# 03_Power.net
KiCad netlist of a schematic drawn in Altium Designer
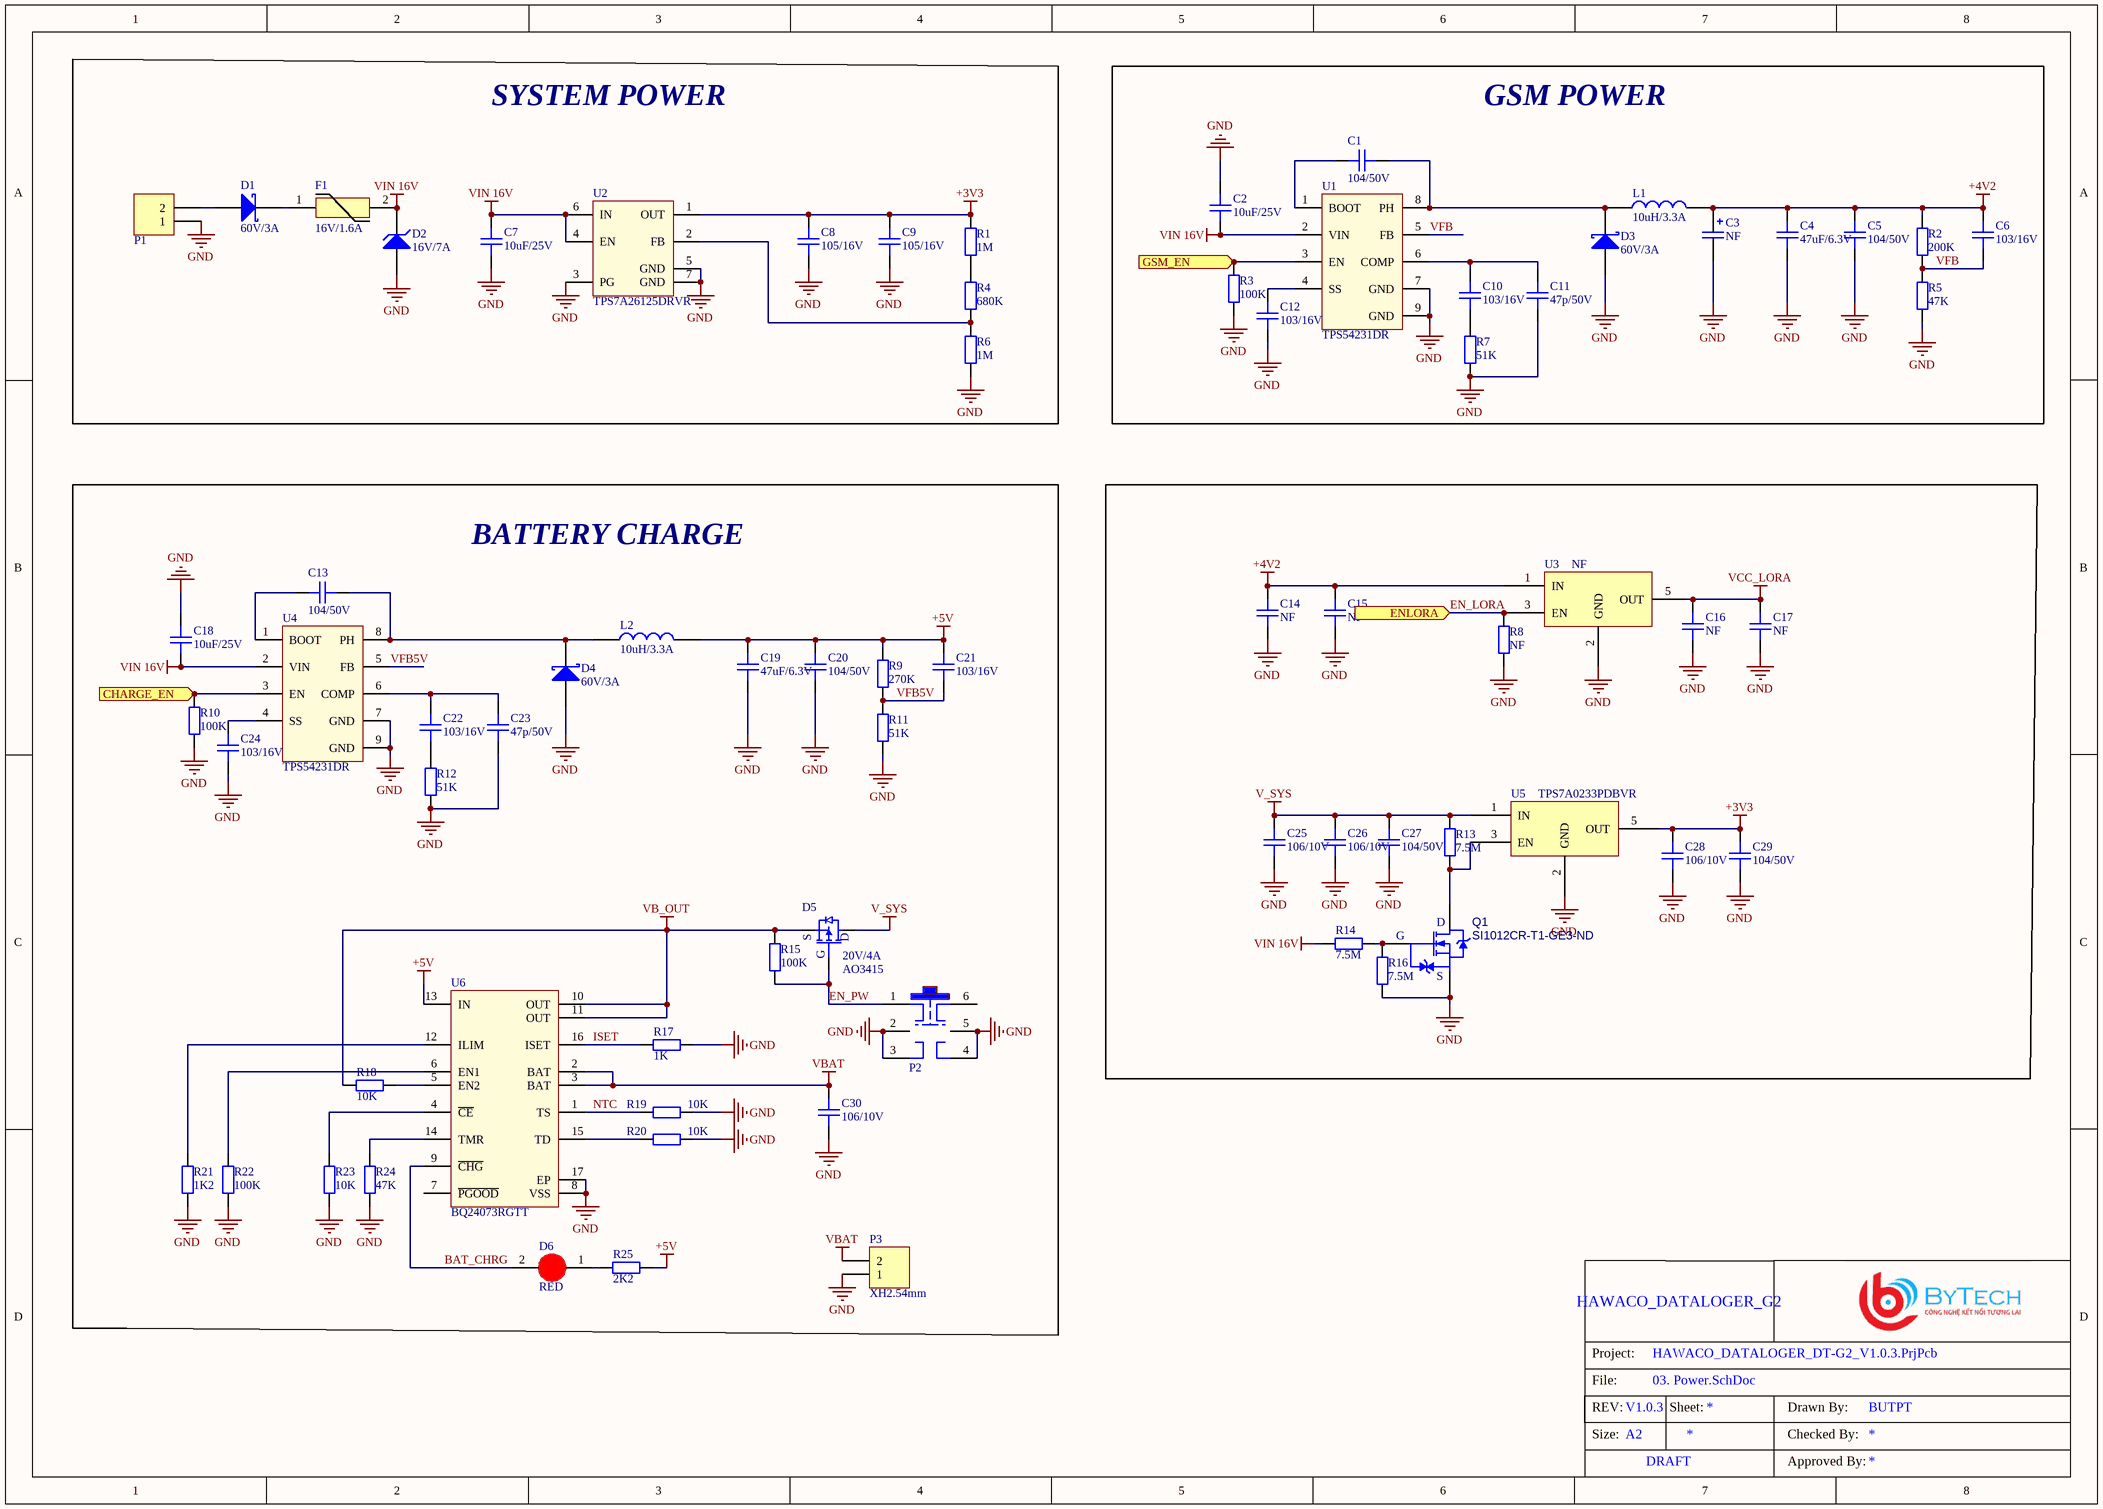
[diagram p0: 03. Power.SchDoc]

(export (version "E")
  (design (tool "Eeschema 10.0.6"))
  (components
    (comp (ref "C1")
      (value "104/50V")
      (footprint "CAPC-0603 (1608)")
      (description "CAP CER 0.1uF 50V 10% X7R 0603")
      (fields (field (name "MPN") "C0603C104K5RACTU"))
      (libsource (lib "01.Passives") (part "C0603C104K5RACTU"))
    )
    (comp (ref "C2")
      (value "10uF/25V")
      (footprint "CAPC-0805 (2012)")
      (description "CAP0805 X5R 10UF 10% 25V")
      (fields (field (name "MPN") "GMC21X5R106K25NT") (field (name "MFR") "CAL-CHIP ELECTRONICS, INC."))
      (libsource (lib "01.Passives") (part "GMC21X5R106K25NT"))
    )
    (comp (ref "C3")
      (value "NF")
      (footprint "CAP_TANTAL_1210(3528)")
      (description "CAP TANT POLY 220uF 20% 6.3V 3528 35mOhm ESR")
      (fields (field (name "MPN") "T520B227M006ATE035"))
      (libsource (lib "01.Passives") (part "T520B227M006ATE035"))
    )
    (comp (ref "C4")
      (value "47uF/6.3V")
      (footprint "CAPC-0603 (1608)")
      (description "CAP CER 47UF 6.3V X5R 0603")
      (fields (field (name "MPN") "GRM188R60J476ME15D") (field (name "MFR") "Murata Electronics"))
      (libsource (lib "01.Passives") (part "GRM188R60J476ME15D"))
    )
    (comp (ref "C5")
      (value "104/50V")
      (footprint "CAPC-0603 (1608)")
      (description "CAP CER 0.1uF 50V 10% X7R 0603")
      (fields (field (name "MPN") "C0603C104K5RACTU"))
      (libsource (lib "01.Passives") (part "C0603C104K5RACTU"))
    )
    (comp (ref "C6")
      (value "103/16V")
      (footprint "CAPC-0603 (1608)")
      (description "CAP CER 10nF 16V 10% X7R 0603")
      (fields (field (name "MPN") "CC0603KRX7R7BB103"))
      (libsource (lib "01.Passives") (part "CC0603KRX7R7BB103"))
    )
    (comp (ref "C7")
      (value "10uF/25V")
      (footprint "CAPC-0805 (2012)")
      (description "CAP0805 X5R 10UF 10% 25V")
      (fields (field (name "MPN") "GMC21X5R106K25NT") (field (name "MFR") "CAL-CHIP ELECTRONICS, INC."))
      (libsource (lib "01.Passives") (part "GMC21X5R106K25NT"))
    )
    (comp (ref "C8")
      (value "105/16V")
      (footprint "CAPC-0603 (1608)")
      (description "CAP CER 1uF 10% 16V X7R 0603")
      (fields (field (name "MPN") "CC0603KRX7R7BB105"))
      (libsource (lib "01.Passives") (part "CC0603KRX7R7BB105"))
    )
    (comp (ref "C9")
      (value "105/16V")
      (footprint "CAPC-0603 (1608)")
      (description "CAP CER 1uF 10% 16V X7R 0603")
      (fields (field (name "MPN") "CC0603KRX7R7BB105"))
      (libsource (lib "01.Passives") (part "CC0603KRX7R7BB105"))
    )
    (comp (ref "C10")
      (value "103/16V")
      (footprint "CAPC-0603 (1608)")
      (description "CAP CER 10nF 16V 10% X7R 0603")
      (fields (field (name "MPN") "CC0603KRX7R7BB103"))
      (libsource (lib "01.Passives") (part "CC0603KRX7R7BB103"))
    )
    (comp (ref "C11")
      (value "47p/50V")
      (footprint "CAPC-0603 (1608)")
      (description "CAP CER 47pF 5% 50V C0G/NP0 0603")
      (fields (field (name "MPN") "CL10C470JB8NNNC"))
      (libsource (lib "01.Passives") (part "CL10C470JB8NNNC"))
    )
    (comp (ref "C12")
      (value "103/16V")
      (footprint "CAPC-0603 (1608)")
      (description "CAP CER 10nF 16V 10% X7R 0603")
      (fields (field (name "MPN") "CC0603KRX7R7BB103"))
      (libsource (lib "01.Passives") (part "CC0603KRX7R7BB103"))
    )
    (comp (ref "C13")
      (value "104/50V")
      (footprint "CAPC-0603 (1608)")
      (description "CAP CER 0.1uF 50V 10% X7R 0603")
      (fields (field (name "MPN") "C0603C104K5RACTU"))
      (libsource (lib "01.Passives") (part "C0603C104K5RACTU"))
    )
    (comp (ref "C14")
      (value "NF")
      (footprint "CAPC-0603 (1608)")
      (description "CAP CER 10uF 10% 10V X5R 0603")
      (fields (field (name "MPN") "CL10A106KP8NNNC"))
      (libsource (lib "01.Passives") (part "CL10A106KP8NNNC"))
    )
    (comp (ref "C15")
      (value "NF")
      (footprint "CAPC-0603 (1608)")
      (description "CAP CER 0.1uF 50V 10% X7R 0603")
      (fields (field (name "MPN") "C0603C104K5RACTU"))
      (libsource (lib "01.Passives") (part "C0603C104K5RACTU"))
    )
    (comp (ref "C16")
      (value "NF")
      (footprint "CAPC-0603 (1608)")
      (description "CAP CER 10uF 10% 10V X5R 0603")
      (fields (field (name "MPN") "CL10A106KP8NNNC"))
      (libsource (lib "01.Passives") (part "CL10A106KP8NNNC"))
    )
    (comp (ref "C17")
      (value "NF")
      (footprint "CAPC-0603 (1608)")
      (description "CAP CER 0.1uF 50V 10% X7R 0603")
      (fields (field (name "MPN") "C0603C104K5RACTU"))
      (libsource (lib "01.Passives") (part "C0603C104K5RACTU"))
    )
    (comp (ref "C18")
      (value "10uF/25V")
      (footprint "CAPC-0805 (2012)")
      (description "CAP0805 X5R 10UF 10% 25V")
      (fields (field (name "MPN") "GMC21X5R106K25NT") (field (name "MFR") "CAL-CHIP ELECTRONICS, INC."))
      (libsource (lib "01.Passives") (part "GMC21X5R106K25NT"))
    )
    (comp (ref "C19")
      (value "47uF/6.3V")
      (footprint "CAPC-0603 (1608)")
      (description "CAP CER 47UF 6.3V X5R 0603")
      (fields (field (name "MPN") "GRM188R60J476ME15D") (field (name "MFR") "Murata Electronics"))
      (libsource (lib "01.Passives") (part "GRM188R60J476ME15D"))
    )
    (comp (ref "C20")
      (value "104/50V")
      (footprint "CAPC-0603 (1608)")
      (description "CAP CER 0.1uF 50V 10% X7R 0603")
      (fields (field (name "MPN") "C0603C104K5RACTU"))
      (libsource (lib "01.Passives") (part "C0603C104K5RACTU"))
    )
    (comp (ref "C21")
      (value "103/16V")
      (footprint "CAPC-0603 (1608)")
      (description "CAP CER 10nF 16V 10% X7R 0603")
      (fields (field (name "MPN") "CC0603KRX7R7BB103"))
      (libsource (lib "01.Passives") (part "CC0603KRX7R7BB103"))
    )
    (comp (ref "C22")
      (value "103/16V")
      (footprint "CAPC-0603 (1608)")
      (description "CAP CER 10nF 16V 10% X7R 0603")
      (fields (field (name "MPN") "CC0603KRX7R7BB103"))
      (libsource (lib "01.Passives") (part "CC0603KRX7R7BB103"))
    )
    (comp (ref "C23")
      (value "47p/50V")
      (footprint "CAPC-0603 (1608)")
      (description "CAP CER 47pF 5% 50V C0G/NP0 0603")
      (fields (field (name "MPN") "CL10C470JB8NNNC"))
      (libsource (lib "01.Passives") (part "CL10C470JB8NNNC"))
    )
    (comp (ref "C24")
      (value "103/16V")
      (footprint "CAPC-0603 (1608)")
      (description "CAP CER 10nF 16V 10% X7R 0603")
      (fields (field (name "MPN") "CC0603KRX7R7BB103"))
      (libsource (lib "01.Passives") (part "CC0603KRX7R7BB103"))
    )
    (comp (ref "C25")
      (value "106/10V")
      (footprint "CAPC-0603 (1608)")
      (description "CAP CER 10uF 10% 10V X5R 0603")
      (fields (field (name "MPN") "CL10A106KP8NNNC"))
      (libsource (lib "01.Passives") (part "CL10A106KP8NNNC"))
    )
    (comp (ref "C26")
      (value "106/10V")
      (footprint "CAPC-0603 (1608)")
      (description "CAP CER 10uF 10% 10V X5R 0603")
      (fields (field (name "MPN") "CL10A106KP8NNNC"))
      (libsource (lib "01.Passives") (part "CL10A106KP8NNNC"))
    )
    (comp (ref "C27")
      (value "104/50V")
      (footprint "CAPC-0603 (1608)")
      (description "CAP CER 0.1uF 50V 10% X7R 0603")
      (fields (field (name "MPN") "C0603C104K5RACTU"))
      (libsource (lib "01.Passives") (part "C0603C104K5RACTU"))
    )
    (comp (ref "C28")
      (value "106/10V")
      (footprint "CAPC-0603 (1608)")
      (description "CAP CER 10uF 10% 10V X5R 0603")
      (fields (field (name "MPN") "CL10A106KP8NNNC"))
      (libsource (lib "01.Passives") (part "CL10A106KP8NNNC"))
    )
    (comp (ref "C29")
      (value "104/50V")
      (footprint "CAPC-0603 (1608)")
      (description "CAP CER 0.1uF 50V 10% X7R 0603")
      (fields (field (name "MPN") "C0603C104K5RACTU"))
      (libsource (lib "01.Passives") (part "C0603C104K5RACTU"))
    )
    (comp (ref "C30")
      (value "106/10V")
      (footprint "CAPC-0603 (1608)")
      (description "CAP CER 10uF 10% 10V X5R 0603")
      (fields (field (name "MPN") "CL10A106KP8NNNC"))
      (libsource (lib "01.Passives") (part "CL10A106KP8NNNC"))
    )
    (comp (ref "D1")
      (value "60V/3A")
      (footprint "DIODE_DO214AC_SMA")
      (description "DIODE SCHOTTKY 60V 3A DO214AC")
      (fields (field (name "MPN") "SK36A-LTP"))
      (libsource (lib "03.Semiconductor") (part "SK36A-LTP"))
    )
    (comp (ref "D2")
      (value "16V/7A")
      (footprint "SOD123")
      (description "TVS DIODE 16VWM 26VC SOD123FL")
      (fields (field (name "MPN") "1SMF16BT3") (field (name "MFR") "ON Semiconductor"))
      (libsource (lib "03.Semiconductor") (part "1SMF16BT3"))
    )
    (comp (ref "D3")
      (value "60V/3A")
      (footprint "DIODE_DO214AC_SMA")
      (description "DIODE SCHOTTKY 60V 3A DO214AC")
      (fields (field (name "MPN") "SK36A-LTP") (field (name "MANUFACTURER") "Micro Commercial Co"))
      (libsource (lib "03.Semiconductor") (part "SK36A-LTP"))
    )
    (comp (ref "D4")
      (value "60V/3A")
      (footprint "DIODE_DO214AC_SMA")
      (description "DIODE SCHOTTKY 60V 3A DO214AC")
      (fields (field (name "MPN") "SK36A-LTP") (field (name "MANUFACTURER") "Micro Commercial Co"))
      (libsource (lib "03.Semiconductor") (part "SK36A-LTP"))
    )
    (comp (ref "D5")
      (value "20V/4A")
      (footprint "SOT23_3")
      (description "MOSFET P-CH 20V 4A SOT23")
      (fields (field (name "MFR") "Alpha & Omega Semiconductor Inc.") (field (name "MPN") "AO3415"))
      (libsource (lib "03.Semiconductor") (part "AO3415"))
    )
    (comp (ref "D6")
      (value "RED")
      (footprint "LED 0603")
      (description "LED 0603 RED")
      (libsource (lib "03.Semiconductor") (part "LED 0603 RED"))
    )
    (comp (ref "F1")
      (value "16V/1.6A")
      (footprint "FUSE_1812(4532)")
      (description "PTC RESET FUSE 16V 1.6A 1812")
      (fields (field (name "MPN") "MPTS1812L16016R") (field (name "MFR") "Meritek"))
      (libsource (lib "02.Power,Protection") (part "MPTS1812L16016R"))
    )
    (comp (ref "L1")
      (value "10uH/3.3A")
      (footprint "IND-74404084150")
      (description "FIXED IND 10UH 3.3A 38 MOHM SMD")
      (fields
        (field (name "MPN") "SWPA8040S100MT")
        (field (name "MFR") "Shenzhen Sunlord Electronics Co., Ltd.")
      )
      (libsource (lib "01.Passives") (part "SWPA8040S100MT"))
    )
    (comp (ref "L2")
      (value "10uH/3.3A")
      (footprint "IND-74404084150")
      (description "FIXED IND 10UH 3.3A 38 MOHM SMD")
      (fields
        (field (name "MPN") "SWPA8040S100MT")
        (field (name "MFR") "Shenzhen Sunlord Electronics Co., Ltd.")
      )
      (libsource (lib "01.Passives") (part "SWPA8040S100MT"))
    )
    (comp (ref "P1")
      (value "15EDG3.81-2P")
      (footprint "HDR_3.81MM_RA_2x1")
      (description "Pluggable terminal 15EDG- 2P 3.81MM")
      (fields (field (name "MFR") "China"))
      (libsource (lib "04.Header-Connecter") (part "15EDG3.81-2P"))
    )
    (comp (ref "P2")
      (value "~")
      (footprint "KFC8x8")
      (description "Self-locking button 6p 8x8mm")
      (fields (field (name "MPN") "KFC8X8") (field (name "MFR") "China"))
      (libsource (lib "08.Miscellaneous") (part "KFC8X8"))
    )
    (comp (ref "P3")
      (value "XH2.54mm")
      (footprint "XH2.54-2P")
      (description "XH2.54mmm - 2P 180 degree")
      (fields (field (name "MPN") "XH-2A"))
      (libsource (lib "04.Header-Connecter") (part "XH-2A"))
    )
    (comp (ref "Q1")
      (value "SI1012CR-T1-GE3-ND")
      (footprint "SOT-416")
      (description "MOSFET N-CH 20V 0.63A SC-75A")
      (libsource (lib "03.Semiconductor") (part "SI1012CR-T1-GE3-ND"))
    )
    (comp (ref "R1")
      (value "1M")
      (footprint "RESC-0603 (1608)")
      (description "RES SMD 1M OHM 1% 1/10W 0603")
      (fields (field (name "MPN") "CRCW06031M00FKEA"))
      (libsource (lib "01.Passives") (part "CRCW06031M00FKEA"))
    )
    (comp (ref "R2")
      (value "200K")
      (footprint "RESC-0603 (1608)")
      (description "RES SMD 200K OHM 1% 1/10W 0603")
      (fields (field (name "MPN") "CR0603-FX-2003ELF"))
      (libsource (lib "01.Passives") (part "CR0603-FX-2003ELF"))
    )
    (comp (ref "R3")
      (value "100K")
      (footprint "RESC-0603 (1608)")
      (description "RES SMD 100K OHM 1% 1/10W 0603")
      (fields (field (name "MPN") "RC0603FR-07100KL"))
      (libsource (lib "01.Passives") (part "RC0603FR-07100KL"))
    )
    (comp (ref "R4")
      (value "680K")
      (footprint "RESC-0603 (1608)")
      (description "RES SMD 680K OHM 1% 1/10W 0603")
      (fields (field (name "MPN") "RT0603FRE07680KL") (field (name "MFR") "YAGEO"))
      (libsource (lib "01.Passives") (part "RT0603FRE07680KL"))
    )
    (comp (ref "R5")
      (value "47K")
      (footprint "RESC-0603 (1608)")
      (description "RES SMD 47K OHM 1% 1/10W 0603")
      (fields (field (name "MPN") "RC0603FR0747KL"))
      (libsource (lib "01.Passives") (part "RC0603FR0747KL"))
    )
    (comp (ref "R6")
      (value "1M")
      (footprint "RESC-0603 (1608)")
      (description "RES SMD 1M OHM 1% 1/10W 0603")
      (fields (field (name "MPN") "CRCW06031M00FKEA"))
      (libsource (lib "01.Passives") (part "CRCW06031M00FKEA"))
    )
    (comp (ref "R7")
      (value "51K")
      (footprint "RESC-0603 (1608)")
      (description "RES SMD 51K OHM 1% 1/10W 0603")
      (fields (field (name "MPN") "RC0603FR-0751KL") (field (name "MFR") "Yageo"))
      (libsource (lib "01.Passives") (part "RC0603FR-0751KL"))
    )
    (comp (ref "R8")
      (value "NF")
      (footprint "RESC-0603 (1608)")
      (description "RES SMD 100K OHM 1% 1/10W 0603")
      (fields (field (name "MPN") "RC0603FR-07100KL"))
      (libsource (lib "01.Passives") (part "RC0603FR-07100KL"))
    )
    (comp (ref "R9")
      (value "270K")
      (footprint "RESC-0603 (1608)")
      (description "RES SMD 270K OHM 0.1% 1/10W 0603")
      (fields (field (name "MPN") "RT0603BRD07270KL"))
      (libsource (lib "01.Passives") (part "RT0603BRD07270KL"))
    )
    (comp (ref "R10")
      (value "100K")
      (footprint "RESC-0603 (1608)")
      (description "RES SMD 100K OHM 1% 1/10W 0603")
      (fields (field (name "MPN") "RC0603FR-07100KL"))
      (libsource (lib "01.Passives") (part "RC0603FR-07100KL"))
    )
    (comp (ref "R11")
      (value "51K")
      (footprint "RESC-0603 (1608)")
      (description "RES SMD 51K OHM 1% 1/10W 0603")
      (fields (field (name "MPN") "RC0603FR-0751KL") (field (name "MFR") "Yageo"))
      (libsource (lib "01.Passives") (part "RC0603FR-0751KL"))
    )
    (comp (ref "R12")
      (value "51K")
      (footprint "RESC-0603 (1608)")
      (description "RES SMD 51K OHM 1% 1/10W 0603")
      (fields (field (name "MPN") "RC0603FR-0751KL") (field (name "MFR") "Yageo"))
      (libsource (lib "01.Passives") (part "RC0603FR-0751KL"))
    )
    (comp (ref "R13")
      (value "7.5M")
      (footprint "RESC-0603 (1608)")
      (description "RES SMD 7.5M OHM 1% 1/10W 0603")
      (fields (field (name "MPN") "RC0603FR-077M5L"))
      (libsource (lib "01.Passives") (part "RC0603FR-077M5L"))
    )
    (comp (ref "R14")
      (value "7.5M")
      (footprint "RESC-0603 (1608)")
      (description "RES SMD 7.5M OHM 1% 1/10W 0603")
      (fields (field (name "MPN") "RC0603FR-077M5L"))
      (libsource (lib "") (part "RC0603FR-077M5L_1"))
    )
    (comp (ref "R15")
      (value "100K")
      (footprint "RESC-0603 (1608)")
      (description "RES SMD 100K OHM 1% 1/10W 0603")
      (fields (field (name "MPN") "RC0603FR-07100KL"))
      (libsource (lib "01.Passives") (part "RC0603FR-07100KL"))
    )
    (comp (ref "R16")
      (value "7.5M")
      (footprint "RESC-0603 (1608)")
      (description "RES SMD 7.5M OHM 1% 1/10W 0603")
      (fields (field (name "MPN") "RC0603FR-077M5L"))
      (libsource (lib "01.Passives") (part "RC0603FR-077M5L"))
    )
    (comp (ref "R17")
      (value "1K")
      (footprint "RESC-0603 (1608)")
      (description "RES SMD 1 KOHM 1% 1/10W 0603")
      (fields (field (name "MPN") "RC0603FR-071KL"))
      (libsource (lib "01.Passives") (part "RC0603FR-071KL"))
    )
    (comp (ref "R18")
      (value "10K")
      (footprint "RESC-0603 (1608)")
      (description "RES SMD 10K OHM 1% 1/10W 0603")
      (fields (field (name "MPN") "RC0603FR-0710KL"))
      (libsource (lib "") (part "RC0603FR-0710KL_1"))
    )
    (comp (ref "R19")
      (value "10K")
      (footprint "RESC-0603 (1608)")
      (description "RES SMD 10K OHM 1% 1/10W 0603")
      (fields (field (name "MPN") "RC0603FR-0710KL"))
      (libsource (lib "") (part "RC0603FR-0710KL_1"))
    )
    (comp (ref "R20")
      (value "10K")
      (footprint "RESC-0603 (1608)")
      (description "RES SMD 10K OHM 1% 1/10W 0603")
      (fields (field (name "MPN") "RC0603FR-0710KL"))
      (libsource (lib "") (part "RC0603FR-0710KL_1"))
    )
    (comp (ref "R21")
      (value "1K2")
      (footprint "RESC-0603 (1608)")
      (description "RES SMD 1.2K OHM 1% 1/10W 0603")
      (fields (field (name "MPN") "RC0603FR-071K2L"))
      (libsource (lib "01.Passives") (part "RC0603FR-071K2L"))
    )
    (comp (ref "R22")
      (value "100K")
      (footprint "RESC-0603 (1608)")
      (description "RES SMD 100K OHM 1% 1/10W 0603")
      (fields (field (name "MPN") "RC0603FR-07100KL"))
      (libsource (lib "01.Passives") (part "RC0603FR-07100KL"))
    )
    (comp (ref "R23")
      (value "10K")
      (footprint "RESC-0603 (1608)")
      (description "RES SMD 10K OHM 1% 1/10W 0603")
      (fields (field (name "MPN") "RC0603FR-0710KL"))
      (libsource (lib "01.Passives") (part "RC0603FR-0710KL"))
    )
    (comp (ref "R24")
      (value "47K")
      (footprint "RESC-0603 (1608)")
      (description "RES SMD 47K OHM 1% 1/10W 0603")
      (fields (field (name "MPN") "RC0603FR0747KL"))
      (libsource (lib "01.Passives") (part "RC0603FR0747KL"))
    )
    (comp (ref "R25")
      (value "2K2")
      (footprint "RESC-0603 (1608)")
      (description "RES SMD 2.2K OHM 1% 1/10W 0603")
      (fields (field (name "MPN") "CRCW06032K20FKEA"))
      (libsource (lib "01.Passives") (part "CRCW06032K20FKEA"))
    )
    (comp (ref "U1")
      (value "TPS54231DR")
      (footprint "SOIC8 - TP")
      (description "IC REG BUCK ADJUSTABLE 2A 8SOIC")
      (fields (field (name "MFR") "TI"))
      (libsource (lib "05.IC") (part "TPS54231DR"))
    )
    (comp (ref "U2")
      (value "TPS7A26125DRVR")
      (footprint "WSON6")
      (description "IC REG LINEAR 1.25V 500MA 6WSON")
      (fields (field (name "MFR") "TI"))
      (libsource (lib "05.IC") (part "TPS7A26125DRVR"))
    )
    (comp (ref "U3")
      (value "NF")
      (footprint "SOT23-5")
      (description "NANOPOWER LDO")
      (fields (field (name "MPN") "TPS7A0233PDBVR"))
      (libsource (lib "05.IC") (part "TPS7A0233PDBVR"))
    )
    (comp (ref "U4")
      (value "TPS54231DR")
      (footprint "SOIC8 - TP")
      (description "IC REG BUCK ADJUSTABLE 2A 8SOIC")
      (fields (field (name "MFR") "TI"))
      (libsource (lib "05.IC") (part "TPS54231DR"))
    )
    (comp (ref "U5")
      (value "TPS7A0233PDBVR")
      (footprint "SOT23-5")
      (description "NANOPOWER LDO")
      (libsource (lib "05.IC") (part "TPS7A0233PDBVR"))
    )
    (comp (ref "U6")
      (value "BQ24073RGTT")
      (footprint "RGT16-1700X1700TP")
      (description "IC LI-ION CHARGE/PWR MGMT 16-QFN")
      (fields (field (name "MFR") "Texas Instruments"))
      (libsource (lib "05.IC") (part "BQ24073RGTT"))
    )
  )
  (nets
    (net (code "1") (name "+3V3") (class "Default")
      (node (ref "C28") (pin "2") (pinfunction "2_2") (pintype "passive"))
      (node (ref "C29") (pin "2") (pinfunction "2_2") (pintype "passive"))
      (node (ref "C8") (pin "2") (pinfunction "2_2") (pintype "passive"))
      (node (ref "C9") (pin "2") (pinfunction "2_2") (pintype "passive"))
      (node (ref "R1") (pin "2") (pinfunction "2_2") (pintype "passive"))
      (node (ref "U2") (pin "1") (pinfunction "OUT_1") (pintype "power_in"))
      (node (ref "U5") (pin "5") (pinfunction "OUT_5") (pintype "passive"))
    )
    (net (code "2") (name "+4V2") (class "Default")
      (node (ref "C14") (pin "2") (pinfunction "2_2") (pintype "passive"))
      (node (ref "C15") (pin "2") (pinfunction "2_2") (pintype "passive"))
      (node (ref "C3") (pin "1") (pinfunction "1_1") (pintype "passive"))
      (node (ref "C4") (pin "2") (pinfunction "2_2") (pintype "passive"))
      (node (ref "C5") (pin "2") (pinfunction "2_2") (pintype "passive"))
      (node (ref "C6") (pin "2") (pinfunction "2_2") (pintype "passive"))
      (node (ref "L1") (pin "2") (pinfunction "2_2") (pintype "passive"))
      (node (ref "R2") (pin "2") (pinfunction "2_2") (pintype "passive"))
      (node (ref "U3") (pin "1") (pinfunction "IN_1") (pintype "passive"))
    )
    (net (code "3") (name "+5V") (class "Default")
      (node (ref "C19") (pin "2") (pinfunction "2_2") (pintype "passive"))
      (node (ref "C20") (pin "2") (pinfunction "2_2") (pintype "passive"))
      (node (ref "C21") (pin "2") (pinfunction "2_2") (pintype "passive"))
      (node (ref "L2") (pin "2") (pinfunction "2_2") (pintype "passive"))
      (node (ref "R25") (pin "2") (pinfunction "2_2") (pintype "passive"))
      (node (ref "R9") (pin "2") (pinfunction "2_2") (pintype "passive"))
      (node (ref "U6") (pin "13") (pinfunction "IN_13") (pintype "power_in"))
    )
    (net (code "4") (name "/BAT_CHRG") (class "Default")
      (node (ref "D6") (pin "2") (pinfunction "K_2") (pintype "passive"))
      (node (ref "U6") (pin "9") (pinfunction "~{CHG}_9") (pintype "power_in"))
    )
    (net (code "5") (name "/CHARGE_EN") (class "Default")
      (node (ref "R10") (pin "2") (pinfunction "2_2") (pintype "passive"))
      (node (ref "U4") (pin "3") (pinfunction "EN_3") (pintype "passive"))
    )
    (net (code "6") (name "/EN_LORA") (class "Default")
      (node (ref "R8") (pin "2") (pinfunction "2_2") (pintype "passive"))
      (node (ref "U3") (pin "3") (pinfunction "EN_3") (pintype "passive"))
    )
    (net (code "7") (name "/EN_PW") (class "Default")
      (node (ref "D5") (pin "1") (pinfunction "G_1") (pintype "passive"))
      (node (ref "P2") (pin "1") (pinfunction "1_1") (pintype "passive"))
      (node (ref "R15") (pin "1") (pinfunction "1_1") (pintype "passive"))
    )
    (net (code "8") (name "/GSM_EN") (class "Default")
      (node (ref "R3") (pin "2") (pinfunction "2_2") (pintype "passive"))
      (node (ref "U1") (pin "3") (pinfunction "EN_3") (pintype "passive"))
    )
    (net (code "9") (name "/ISET") (class "Default")
      (node (ref "R17") (pin "1") (pinfunction "1_1") (pintype "passive"))
      (node (ref "U6") (pin "16") (pinfunction "ISET_16") (pintype "power_in"))
    )
    (net (code "10") (name "/NTC") (class "Default")
      (node (ref "R19") (pin "1") (pinfunction "1_1") (pintype "passive"))
      (node (ref "U6") (pin "1") (pinfunction "TS_1") (pintype "power_in"))
    )
    (net (code "11") (name "/VFB") (class "Default")
      (node (ref "C6") (pin "1") (pinfunction "1_1") (pintype "passive"))
      (node (ref "R2") (pin "1") (pinfunction "1_1") (pintype "passive"))
      (node (ref "R5") (pin "2") (pinfunction "2_2") (pintype "passive"))
      (node (ref "U1") (pin "5") (pinfunction "FB_5") (pintype "power_in"))
    )
    (net (code "12") (name "/VFB5V") (class "Default")
      (node (ref "C21") (pin "1") (pinfunction "1_1") (pintype "passive"))
      (node (ref "R11") (pin "2") (pinfunction "2_2") (pintype "passive"))
      (node (ref "R9") (pin "1") (pinfunction "1_1") (pintype "passive"))
      (node (ref "U4") (pin "5") (pinfunction "FB_5") (pintype "power_in"))
    )
    (net (code "13") (name "GND") (class "Default")
      (node (ref "C11") (pin "1") (pinfunction "1_1") (pintype "passive"))
      (node (ref "C12") (pin "2") (pinfunction "2_2") (pintype "passive"))
      (node (ref "C14") (pin "1") (pinfunction "1_1") (pintype "passive"))
      (node (ref "C15") (pin "1") (pinfunction "1_1") (pintype "passive"))
      (node (ref "C16") (pin "1") (pinfunction "1_1") (pintype "passive"))
      (node (ref "C17") (pin "1") (pinfunction "1_1") (pintype "passive"))
      (node (ref "C18") (pin "1") (pinfunction "1_1") (pintype "passive"))
      (node (ref "C19") (pin "1") (pinfunction "1_1") (pintype "passive"))
      (node (ref "C2") (pin "1") (pinfunction "1_1") (pintype "passive"))
      (node (ref "C20") (pin "1") (pinfunction "1_1") (pintype "passive"))
      (node (ref "C23") (pin "1") (pinfunction "1_1") (pintype "passive"))
      (node (ref "C24") (pin "2") (pinfunction "2_2") (pintype "passive"))
      (node (ref "C25") (pin "1") (pinfunction "1_1") (pintype "passive"))
      (node (ref "C26") (pin "1") (pinfunction "1_1") (pintype "passive"))
      (node (ref "C27") (pin "1") (pinfunction "1_1") (pintype "passive"))
      (node (ref "C28") (pin "1") (pinfunction "1_1") (pintype "passive"))
      (node (ref "C29") (pin "1") (pinfunction "1_1") (pintype "passive"))
      (node (ref "C3") (pin "2") (pinfunction "2_2") (pintype "passive"))
      (node (ref "C30") (pin "1") (pinfunction "1_1") (pintype "passive"))
      (node (ref "C4") (pin "1") (pinfunction "1_1") (pintype "passive"))
      (node (ref "C5") (pin "1") (pinfunction "1_1") (pintype "passive"))
      (node (ref "C7") (pin "1") (pinfunction "1_1") (pintype "passive"))
      (node (ref "C8") (pin "1") (pinfunction "1_1") (pintype "passive"))
      (node (ref "C9") (pin "1") (pinfunction "1_1") (pintype "passive"))
      (node (ref "D2") (pin "1") (pinfunction "A_1") (pintype "passive"))
      (node (ref "D3") (pin "1") (pinfunction "A_1") (pintype "passive"))
      (node (ref "D4") (pin "1") (pinfunction "A_1") (pintype "passive"))
      (node (ref "P1") (pin "1") (pinfunction "1_1") (pintype "passive"))
      (node (ref "P2") (pin "2") (pinfunction "2_2") (pintype "passive"))
      (node (ref "P2") (pin "3") (pinfunction "3_3") (pintype "passive"))
      (node (ref "P2") (pin "4") (pinfunction "4_4") (pintype "passive"))
      (node (ref "P2") (pin "5") (pinfunction "5_5") (pintype "passive"))
      (node (ref "P3") (pin "1") (pinfunction "1_1") (pintype "passive"))
      (node (ref "Q1") (pin "2") (pinfunction "S_2") (pintype "passive"))
      (node (ref "R10") (pin "1") (pinfunction "1_1") (pintype "passive"))
      (node (ref "R11") (pin "1") (pinfunction "1_1") (pintype "passive"))
      (node (ref "R12") (pin "1") (pinfunction "1_1") (pintype "passive"))
      (node (ref "R16") (pin "1") (pinfunction "1_1") (pintype "passive"))
      (node (ref "R17") (pin "2") (pinfunction "2_2") (pintype "passive"))
      (node (ref "R19") (pin "2") (pinfunction "2_2") (pintype "passive"))
      (node (ref "R20") (pin "2") (pinfunction "2_2") (pintype "passive"))
      (node (ref "R21") (pin "1") (pinfunction "1_1") (pintype "passive"))
      (node (ref "R22") (pin "1") (pinfunction "1_1") (pintype "passive"))
      (node (ref "R23") (pin "1") (pinfunction "1_1") (pintype "passive"))
      (node (ref "R24") (pin "1") (pinfunction "1_1") (pintype "passive"))
      (node (ref "R3") (pin "1") (pinfunction "1_1") (pintype "passive"))
      (node (ref "R5") (pin "1") (pinfunction "1_1") (pintype "passive"))
      (node (ref "R6") (pin "1") (pinfunction "1_1") (pintype "passive"))
      (node (ref "R7") (pin "1") (pinfunction "1_1") (pintype "passive"))
      (node (ref "R8") (pin "1") (pinfunction "1_1") (pintype "passive"))
      (node (ref "U1") (pin "7") (pinfunction "GND_7") (pintype "power_in"))
      (node (ref "U1") (pin "9") (pinfunction "GND_9") (pintype "power_in"))
      (node (ref "U2") (pin "3") (pinfunction "PG_3") (pintype "power_in"))
      (node (ref "U2") (pin "5") (pinfunction "GND_5") (pintype "power_in"))
      (node (ref "U2") (pin "7") (pinfunction "GND_7") (pintype "power_in"))
      (node (ref "U3") (pin "2") (pinfunction "GND_2") (pintype "passive"))
      (node (ref "U4") (pin "7") (pinfunction "GND_7") (pintype "power_in"))
      (node (ref "U4") (pin "9") (pinfunction "GND_9") (pintype "power_in"))
      (node (ref "U5") (pin "2") (pinfunction "GND_2") (pintype "passive"))
      (node (ref "U6") (pin "17") (pinfunction "EP_17") (pintype "power_in"))
      (node (ref "U6") (pin "8") (pinfunction "VSS_8") (pintype "power_in"))
    )
    (net (code "14") (name "Net-(C10-Pad2)") (class "Default")
      (node (ref "C10") (pin "2") (pinfunction "2_2") (pintype "passive"))
      (node (ref "R7") (pin "2") (pinfunction "2_2") (pintype "passive"))
    )
    (net (code "15") (name "Net-(C22-Pad2)") (class "Default")
      (node (ref "C22") (pin "2") (pinfunction "2_2") (pintype "passive"))
      (node (ref "R12") (pin "2") (pinfunction "2_2") (pintype "passive"))
    )
    (net (code "16") (name "Net-(D1-A)") (class "Default")
      (node (ref "D1") (pin "1") (pinfunction "A_1") (pintype "passive"))
      (node (ref "P1") (pin "2") (pinfunction "2_2") (pintype "passive"))
    )
    (net (code "17") (name "Net-(D1-K)") (class "Default")
      (node (ref "D1") (pin "2") (pinfunction "K_2") (pintype "passive"))
      (node (ref "F1") (pin "1") (pinfunction "1_1") (pintype "passive"))
    )
    (net (code "18") (name "Net-(D3-K)") (class "Default")
      (node (ref "C1") (pin "2") (pinfunction "2_2") (pintype "passive"))
      (node (ref "D3") (pin "2") (pinfunction "K_2") (pintype "passive"))
      (node (ref "L1") (pin "1") (pinfunction "1_1") (pintype "passive"))
      (node (ref "U1") (pin "8") (pinfunction "PH_8") (pintype "power_in"))
    )
    (net (code "19") (name "Net-(D4-K)") (class "Default")
      (node (ref "C13") (pin "2") (pinfunction "2_2") (pintype "passive"))
      (node (ref "D4") (pin "2") (pinfunction "K_2") (pintype "passive"))
      (node (ref "L2") (pin "1") (pinfunction "1_1") (pintype "passive"))
      (node (ref "U4") (pin "8") (pinfunction "PH_8") (pintype "power_in"))
    )
    (net (code "20") (name "Net-(D6-A)") (class "Default")
      (node (ref "D6") (pin "1") (pinfunction "A_1") (pintype "passive"))
      (node (ref "R25") (pin "1") (pinfunction "1_1") (pintype "passive"))
    )
    (net (code "21") (name "Net-(Q1-D)") (class "Default")
      (node (ref "Q1") (pin "3") (pinfunction "D_3") (pintype "passive"))
      (node (ref "R13") (pin "1") (pinfunction "1_1") (pintype "passive"))
      (node (ref "U5") (pin "3") (pinfunction "EN_3") (pintype "passive"))
    )
    (net (code "22") (name "Net-(Q1-G)") (class "Default")
      (node (ref "Q1") (pin "1") (pinfunction "G_1") (pintype "passive"))
      (node (ref "R14") (pin "1") (pinfunction "1_1") (pintype "passive"))
      (node (ref "R16") (pin "2") (pinfunction "2_2") (pintype "passive"))
    )
    (net (code "23") (name "Net-(R1-Pad1)") (class "Default")
      (node (ref "R1") (pin "1") (pinfunction "1_1") (pintype "passive"))
      (node (ref "R4") (pin "2") (pinfunction "2_2") (pintype "passive"))
    )
    (net (code "24") (name "Net-(U1-BOOT)") (class "Default")
      (node (ref "C1") (pin "1") (pinfunction "1_1") (pintype "passive"))
      (node (ref "U1") (pin "1") (pinfunction "BOOT_1") (pintype "power_in"))
    )
    (net (code "25") (name "Net-(U1-COMP)") (class "Default")
      (node (ref "C10") (pin "1") (pinfunction "1_1") (pintype "passive"))
      (node (ref "C11") (pin "2") (pinfunction "2_2") (pintype "passive"))
      (node (ref "U1") (pin "6") (pinfunction "COMP_6") (pintype "power_in"))
    )
    (net (code "26") (name "Net-(U1-SS)") (class "Default")
      (node (ref "C12") (pin "1") (pinfunction "1_1") (pintype "passive"))
      (node (ref "U1") (pin "4") (pinfunction "SS_4") (pintype "power_in"))
    )
    (net (code "27") (name "Net-(U2-FB)") (class "Default")
      (node (ref "R4") (pin "1") (pinfunction "1_1") (pintype "passive"))
      (node (ref "R6") (pin "2") (pinfunction "2_2") (pintype "passive"))
      (node (ref "U2") (pin "2") (pinfunction "FB_2") (pintype "power_in"))
    )
    (net (code "28") (name "Net-(U4-BOOT)") (class "Default")
      (node (ref "C13") (pin "1") (pinfunction "1_1") (pintype "passive"))
      (node (ref "U4") (pin "1") (pinfunction "BOOT_1") (pintype "power_in"))
    )
    (net (code "29") (name "Net-(U4-COMP)") (class "Default")
      (node (ref "C22") (pin "1") (pinfunction "1_1") (pintype "passive"))
      (node (ref "C23") (pin "2") (pinfunction "2_2") (pintype "passive"))
      (node (ref "U4") (pin "6") (pinfunction "COMP_6") (pintype "power_in"))
    )
    (net (code "30") (name "Net-(U4-SS)") (class "Default")
      (node (ref "C24") (pin "1") (pinfunction "1_1") (pintype "passive"))
      (node (ref "U4") (pin "4") (pinfunction "SS_4") (pintype "power_in"))
    )
    (net (code "31") (name "Net-(U6-EN1)") (class "Default")
      (node (ref "R22") (pin "2") (pinfunction "2_2") (pintype "passive"))
      (node (ref "U6") (pin "6") (pinfunction "EN1_6") (pintype "power_in"))
    )
    (net (code "32") (name "Net-(U6-EN2)") (class "Default")
      (node (ref "R18") (pin "2") (pinfunction "2_2") (pintype "passive"))
      (node (ref "U6") (pin "5") (pinfunction "EN2_5") (pintype "power_in"))
    )
    (net (code "33") (name "Net-(U6-ILIM)") (class "Default")
      (node (ref "R21") (pin "2") (pinfunction "2_2") (pintype "passive"))
      (node (ref "U6") (pin "12") (pinfunction "ILIM_12") (pintype "power_in"))
    )
    (net (code "34") (name "Net-(U6-TD)") (class "Default")
      (node (ref "R20") (pin "1") (pinfunction "1_1") (pintype "passive"))
      (node (ref "U6") (pin "15") (pinfunction "TD_15") (pintype "power_in"))
    )
    (net (code "35") (name "Net-(U6-TMR)") (class "Default")
      (node (ref "R24") (pin "2") (pinfunction "2_2") (pintype "passive"))
      (node (ref "U6") (pin "14") (pinfunction "TMR_14") (pintype "power_in"))
    )
    (net (code "36") (name "Net-(U6-~{CE})") (class "Default")
      (node (ref "R23") (pin "2") (pinfunction "2_2") (pintype "passive"))
      (node (ref "U6") (pin "4") (pinfunction "~{CE}_4") (pintype "passive"))
    )
    (net (code "37") (name "VBAT") (class "Default")
      (node (ref "C30") (pin "2") (pinfunction "2_2") (pintype "passive"))
      (node (ref "P3") (pin "2") (pinfunction "2_2") (pintype "passive"))
      (node (ref "U6") (pin "2") (pinfunction "BAT_2") (pintype "power_in"))
      (node (ref "U6") (pin "3") (pinfunction "BAT_3") (pintype "power_in"))
    )
    (net (code "38") (name "VB_OUT") (class "Default")
      (node (ref "D5") (pin "2") (pinfunction "S_2") (pintype "passive"))
      (node (ref "R15") (pin "2") (pinfunction "2_2") (pintype "passive"))
      (node (ref "R18") (pin "1") (pinfunction "1_1") (pintype "passive"))
      (node (ref "U6") (pin "10") (pinfunction "OUT_10") (pintype "power_in"))
      (node (ref "U6") (pin "11") (pinfunction "OUT_11") (pintype "power_in"))
    )
    (net (code "39") (name "VCC_LORA") (class "Default")
      (node (ref "C16") (pin "2") (pinfunction "2_2") (pintype "passive"))
      (node (ref "C17") (pin "2") (pinfunction "2_2") (pintype "passive"))
      (node (ref "U3") (pin "5") (pinfunction "OUT_5") (pintype "passive"))
    )
    (net (code "40") (name "VIN 16V") (class "Default")
      (node (ref "C18") (pin "2") (pinfunction "2_2") (pintype "passive"))
      (node (ref "C2") (pin "2") (pinfunction "2_2") (pintype "passive"))
      (node (ref "C7") (pin "2") (pinfunction "2_2") (pintype "passive"))
      (node (ref "D2") (pin "2") (pinfunction "K_2") (pintype "passive"))
      (node (ref "F1") (pin "2") (pinfunction "2_2") (pintype "passive"))
      (node (ref "R14") (pin "2") (pinfunction "2_2") (pintype "passive"))
      (node (ref "U1") (pin "2") (pinfunction "VIN_2") (pintype "power_in"))
      (node (ref "U2") (pin "4") (pinfunction "EN_4") (pintype "power_in"))
      (node (ref "U2") (pin "6") (pinfunction "IN_6") (pintype "power_in"))
      (node (ref "U4") (pin "2") (pinfunction "VIN_2") (pintype "power_in"))
    )
    (net (code "41") (name "V_SYS") (class "Default")
      (node (ref "C25") (pin "2") (pinfunction "2_2") (pintype "passive"))
      (node (ref "C26") (pin "2") (pinfunction "2_2") (pintype "passive"))
      (node (ref "C27") (pin "2") (pinfunction "2_2") (pintype "passive"))
      (node (ref "D5") (pin "3") (pinfunction "D_3") (pintype "passive"))
      (node (ref "R13") (pin "2") (pinfunction "2_2") (pintype "passive"))
      (node (ref "U5") (pin "1") (pinfunction "IN_1") (pintype "passive"))
    )
    (net (code "42") (name "unconnected-(P2-Pad6)") (class "Default")
      (node (ref "P2") (pin "6") (pinfunction "6_6") (pintype "passive"))
    )
    (net (code "43") (name "unconnected-(U6-~{PGOOD}-Pad7)") (class "Default")
      (node (ref "U6") (pin "7") (pinfunction "~{PGOOD}_7") (pintype "power_in"))
    )
  )
)
